# B0_14CN3801.net
KiCad netlist of a schematic drawn in EAGLE
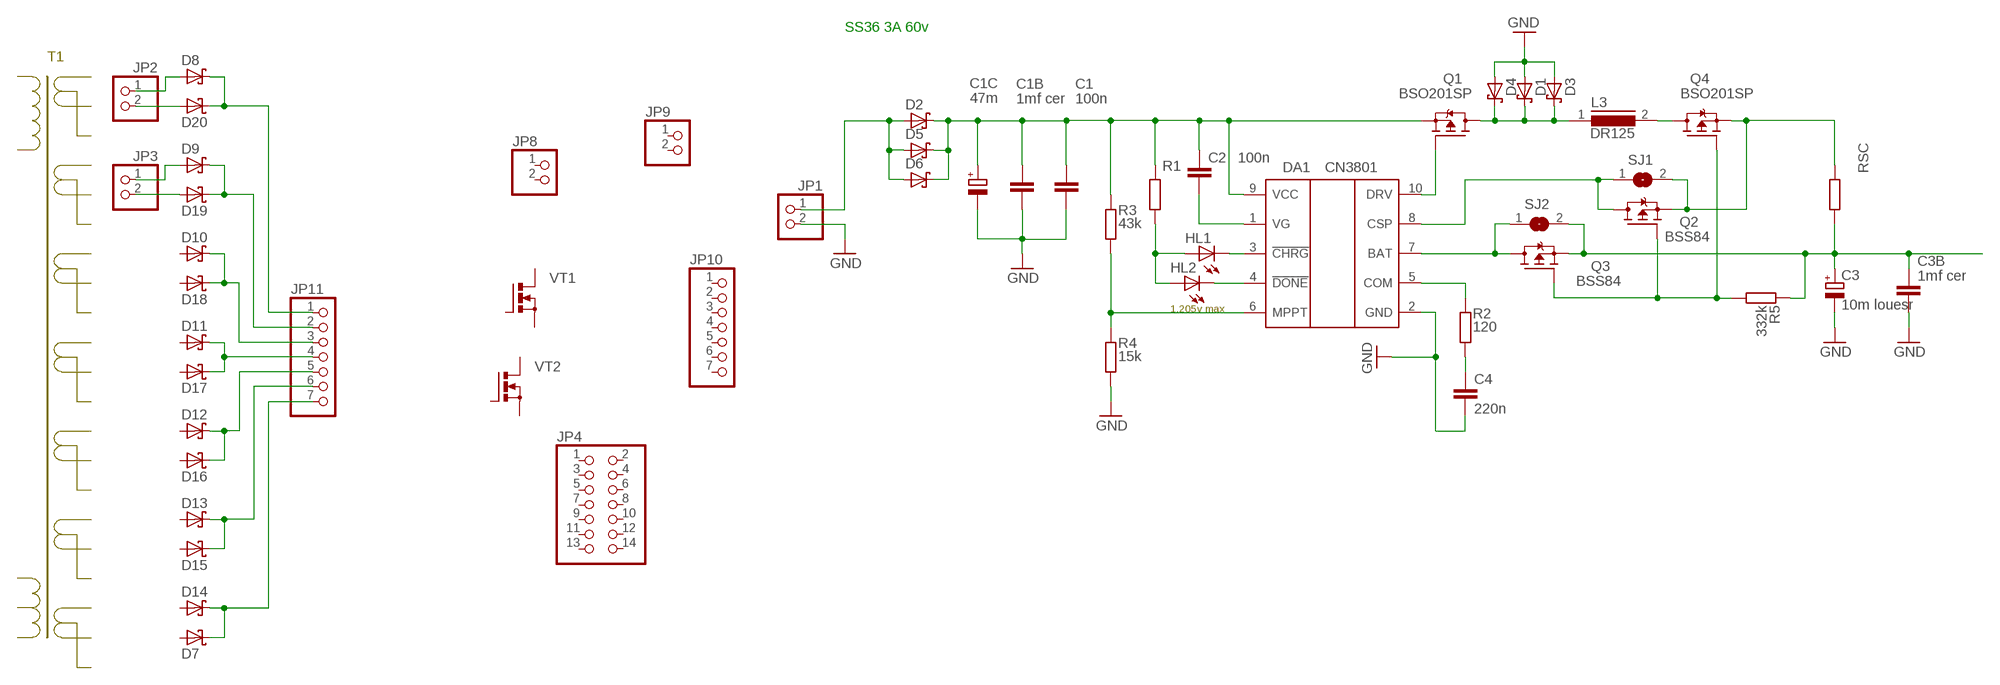
[diagram p0: schematic, sheet 1]

(export (version "E")
  (design (tool "Eeschema 10.0.6"))
  (components
    (comp (ref "C1")
      (value "100n")
      (footprint "eagle-import:C0805")
      (libsource (lib "eagle-import") (part "C-EUC0805"))
    )
    (comp (ref "C1B")
      (value "1mf cer")
      (footprint "eagle-import:C0805")
      (libsource (lib "eagle-import") (part "C-EUC0805"))
    )
    (comp (ref "C1C")
      (value "47m")
      (footprint "eagle-import:E2,5-6")
      (libsource (lib "eagle-import") (part "CPOL-EUE2.5-6"))
    )
    (comp (ref "C2")
      (value "100n")
      (footprint "eagle-import:C0805")
      (libsource (lib "eagle-import") (part "C-EUC0805"))
    )
    (comp (ref "C3")
      (value "10m louesr")
      (footprint "eagle-import:E2,5-6")
      (libsource (lib "eagle-import") (part "CPOL-EUE2.5-6"))
    )
    (comp (ref "C3B")
      (value "1mf cer")
      (footprint "eagle-import:C0805")
      (libsource (lib "eagle-import") (part "C-EUC0805"))
    )
    (comp (ref "C4")
      (value "220n")
      (footprint "eagle-import:C0805")
      (libsource (lib "eagle-import") (part "C-EUC0805"))
    )
    (comp (ref "D1")
      (value "SCHOTTKY-DIODESMC")
      (footprint "eagle-import:SMC")
      (libsource (lib "eagle-import") (part "SCHOTTKY-DIODESMC"))
    )
    (comp (ref "D2")
      (value "SCHOTTKY-DIODESMC")
      (footprint "eagle-import:SMC")
      (libsource (lib "eagle-import") (part "SCHOTTKY-DIODESMC"))
    )
    (comp (ref "D3")
      (value "SCHOTTKY-DIODESMC")
      (footprint "eagle-import:SMC")
      (libsource (lib "eagle-import") (part "SCHOTTKY-DIODESMC"))
    )
    (comp (ref "D4")
      (value "SCHOTTKY-DIODESMC")
      (footprint "eagle-import:SMC")
      (libsource (lib "eagle-import") (part "SCHOTTKY-DIODESMC"))
    )
    (comp (ref "D5")
      (value "SCHOTTKY-DIODESMC")
      (footprint "eagle-import:SMC")
      (libsource (lib "eagle-import") (part "SCHOTTKY-DIODESMC"))
    )
    (comp (ref "D6")
      (value "SCHOTTKY-DIODESMC")
      (footprint "eagle-import:SMC")
      (libsource (lib "eagle-import") (part "SCHOTTKY-DIODESMC"))
    )
    (comp (ref "D7")
      (value "SCHOTTKY-DIODESMC")
      (footprint "eagle-import:SMC")
      (libsource (lib "eagle-import") (part "SCHOTTKY-DIODESMC"))
    )
    (comp (ref "D8")
      (value "SCHOTTKY-DIODESMC")
      (footprint "eagle-import:SMC")
      (libsource (lib "eagle-import") (part "SCHOTTKY-DIODESMC"))
    )
    (comp (ref "D9")
      (value "SCHOTTKY-DIODESMC")
      (footprint "eagle-import:SMC")
      (libsource (lib "eagle-import") (part "SCHOTTKY-DIODESMC"))
    )
    (comp (ref "D10")
      (value "SCHOTTKY-DIODESMC")
      (footprint "eagle-import:SMC")
      (libsource (lib "eagle-import") (part "SCHOTTKY-DIODESMC"))
    )
    (comp (ref "D11")
      (value "SCHOTTKY-DIODESMC")
      (footprint "eagle-import:SMC")
      (libsource (lib "eagle-import") (part "SCHOTTKY-DIODESMC"))
    )
    (comp (ref "D12")
      (value "SCHOTTKY-DIODESMC")
      (footprint "eagle-import:SMC")
      (libsource (lib "eagle-import") (part "SCHOTTKY-DIODESMC"))
    )
    (comp (ref "D13")
      (value "SCHOTTKY-DIODESMC")
      (footprint "eagle-import:SMC")
      (libsource (lib "eagle-import") (part "SCHOTTKY-DIODESMC"))
    )
    (comp (ref "D14")
      (value "SCHOTTKY-DIODESMC")
      (footprint "eagle-import:SMC")
      (libsource (lib "eagle-import") (part "SCHOTTKY-DIODESMC"))
    )
    (comp (ref "D15")
      (value "SCHOTTKY-DIODESMC")
      (footprint "eagle-import:SMC")
      (libsource (lib "eagle-import") (part "SCHOTTKY-DIODESMC"))
    )
    (comp (ref "D16")
      (value "SCHOTTKY-DIODESMC")
      (footprint "eagle-import:SMC")
      (libsource (lib "eagle-import") (part "SCHOTTKY-DIODESMC"))
    )
    (comp (ref "D17")
      (value "SCHOTTKY-DIODESMC")
      (footprint "eagle-import:SMC")
      (libsource (lib "eagle-import") (part "SCHOTTKY-DIODESMC"))
    )
    (comp (ref "D18")
      (value "SCHOTTKY-DIODESMC")
      (footprint "eagle-import:SMC")
      (libsource (lib "eagle-import") (part "SCHOTTKY-DIODESMC"))
    )
    (comp (ref "D19")
      (value "SCHOTTKY-DIODESMC")
      (footprint "eagle-import:SMC")
      (libsource (lib "eagle-import") (part "SCHOTTKY-DIODESMC"))
    )
    (comp (ref "D20")
      (value "SCHOTTKY-DIODESMC")
      (footprint "eagle-import:SMC")
      (libsource (lib "eagle-import") (part "SCHOTTKY-DIODESMC"))
    )
    (comp (ref "DA1")
      (value "CN3801")
      (footprint "eagle-import:SSOP10")
      (libsource (lib "eagle-import") (part "CN3801"))
    )
    (comp (ref "HL1")
      (value "LEDCHIPLED_0603")
      (footprint "eagle-import:CHIPLED_0603")
      (libsource (lib "eagle-import") (part "LEDCHIPLED_0603"))
    )
    (comp (ref "HL2")
      (value "LEDCHIPLED_0603")
      (footprint "eagle-import:CHIPLED_0603")
      (libsource (lib "eagle-import") (part "LEDCHIPLED_0603"))
    )
    (comp (ref "JP1")
      (value "PINHD-1X2/2")
      (footprint "eagle-import:1X02")
      (libsource (lib "eagle-import") (part "PINHD-1X2/2"))
    )
    (comp (ref "JP2")
      (value "PINHD-1X2/2")
      (footprint "eagle-import:1X02")
      (libsource (lib "eagle-import") (part "PINHD-1X2/2"))
    )
    (comp (ref "JP3")
      (value "PINHD-1X2/2")
      (footprint "eagle-import:1X02")
      (libsource (lib "eagle-import") (part "PINHD-1X2/2"))
    )
    (comp (ref "JP4")
      (value "PINHD-2X7")
      (footprint "eagle-import:2X07")
      (libsource (lib "eagle-import") (part "PINHD-2X7"))
    )
    (comp (ref "JP8")
      (value "PINHD-1X2/2")
      (footprint "eagle-import:1X02")
      (libsource (lib "eagle-import") (part "PINHD-1X2/2"))
    )
    (comp (ref "JP9")
      (value "PINHD-1X2/2")
      (footprint "eagle-import:1X02")
      (libsource (lib "eagle-import") (part "PINHD-1X2/2"))
    )
    (comp (ref "JP10")
      (value "PINHD-1X7")
      (footprint "eagle-import:1X07")
      (libsource (lib "eagle-import") (part "PINHD-1X7"))
    )
    (comp (ref "JP11")
      (value "PINHD-1X7")
      (footprint "eagle-import:1X07")
      (libsource (lib "eagle-import") (part "PINHD-1X7"))
    )
    (comp (ref "L3")
      (value "DR125")
      (footprint "eagle-import:DR125")
      (libsource (lib "eagle-import") (part "DR125"))
    )
    (comp (ref "Q1")
      (value "BSO201SP")
      (footprint "eagle-import:SO-8")
      (libsource (lib "eagle-import") (part "BSO201SP"))
    )
    (comp (ref "Q2")
      (value "BSS84")
      (footprint "eagle-import:SC75_INFINEON")
      (libsource (lib "eagle-import") (part "BSA223SP"))
    )
    (comp (ref "Q3")
      (value "BSS84")
      (footprint "eagle-import:SC75_INFINEON")
      (libsource (lib "eagle-import") (part "BSA223SP"))
    )
    (comp (ref "Q4")
      (value "BSO201SP")
      (footprint "eagle-import:SO-8")
      (libsource (lib "eagle-import") (part "BSO201SP"))
    )
    (comp (ref "R1")
      (value "R-EU_R0805")
      (footprint "eagle-import:R0805")
      (libsource (lib "eagle-import") (part "R-EU_R0805"))
    )
    (comp (ref "R2")
      (value "120")
      (footprint "eagle-import:R0805")
      (libsource (lib "eagle-import") (part "R-EU_R0805"))
    )
    (comp (ref "R3")
      (value "43k")
      (footprint "eagle-import:R0805")
      (libsource (lib "eagle-import") (part "R-EU_R0805"))
    )
    (comp (ref "R4")
      (value "15k")
      (footprint "eagle-import:R0805")
      (libsource (lib "eagle-import") (part "R-EU_R0805"))
    )
    (comp (ref "R5")
      (value "332k")
      (footprint "eagle-import:R0805")
      (libsource (lib "eagle-import") (part "R-EU_R0805"))
    )
    (comp (ref "RSC")
      (value "R-EU_R0805")
      (footprint "eagle-import:R0805")
      (libsource (lib "eagle-import") (part "R-EU_R0805"))
    )
    (comp (ref "SJ1") (value "SJ") (footprint "eagle-import:SJ") (libsource (lib "eagle-import") (part "SJ")))
    (comp (ref "SJ2") (value "SJ") (footprint "eagle-import:SJ") (libsource (lib "eagle-import") (part "SJ")))
    (comp (ref "VT1")
      (value "MOSFET-N_TO220_H")
      (footprint "eagle-import:TO220BH")
      (libsource (lib "eagle-import") (part "MOSFET-N_TO220_H"))
    )
    (comp (ref "VT2")
      (value "MOSFET-N_TO220_H")
      (footprint "eagle-import:TO220BH")
      (libsource (lib "eagle-import") (part "MOSFET-N_TO220_H"))
    )
  )
  (nets
    (net (code "1") (name "GND") (class "Default")
      (node (ref "C1") (pin "2") (pinfunction "2_2") (pintype "passive"))
      (node (ref "C1B") (pin "2") (pinfunction "2_2") (pintype "passive"))
      (node (ref "C1C") (pin "-") (pinfunction "-_-") (pintype "passive"))
      (node (ref "C3") (pin "-") (pinfunction "-_-") (pintype "passive"))
      (node (ref "C3B") (pin "2") (pinfunction "2_2") (pintype "passive"))
      (node (ref "C4") (pin "2") (pinfunction "2_2") (pintype "passive"))
      (node (ref "D1") (pin "A") (pinfunction "A_A") (pintype "passive"))
      (node (ref "D3") (pin "A") (pinfunction "A_A") (pintype "passive"))
      (node (ref "D4") (pin "A") (pinfunction "A_A") (pintype "passive"))
      (node (ref "DA1") (pin "2") (pinfunction "GND_2") (pintype "power_in"))
      (node (ref "JP1") (pin "2") (pinfunction "2_2") (pintype "passive"))
      (node (ref "R4") (pin "1") (pinfunction "1_1") (pintype "passive"))
    )
    (net (code "2") (name "Net-(C4-Pad1)") (class "Default")
      (node (ref "C4") (pin "1") (pinfunction "1_1") (pintype "passive"))
      (node (ref "R2") (pin "1") (pinfunction "1_1") (pintype "passive"))
    )
    (net (code "3") (name "Net-(D1-PadC)") (class "Default")
      (node (ref "D1") (pin "C") (pinfunction "C_C") (pintype "passive"))
      (node (ref "D3") (pin "C") (pinfunction "C_C") (pintype "passive"))
      (node (ref "D4") (pin "C") (pinfunction "C_C") (pintype "passive"))
      (node (ref "L3") (pin "1") (pinfunction "1_1") (pintype "passive"))
      (node (ref "Q1") (pin "5") (pinfunction "D_5") (pintype "passive"))
      (node (ref "Q1") (pin "6") (pinfunction "D_6") (pintype "passive"))
      (node (ref "Q1") (pin "7") (pinfunction "D_7") (pintype "passive"))
      (node (ref "Q1") (pin "8") (pinfunction "D_8") (pintype "passive"))
    )
    (net (code "4") (name "Net-(D2-PadA)") (class "Default")
      (node (ref "D2") (pin "A") (pinfunction "A_A") (pintype "passive"))
      (node (ref "D5") (pin "A") (pinfunction "A_A") (pintype "passive"))
      (node (ref "D6") (pin "A") (pinfunction "A_A") (pintype "passive"))
      (node (ref "JP1") (pin "1") (pinfunction "1_1") (pintype "passive"))
    )
    (net (code "5") (name "Net-(D8-PadA)") (class "Default")
      (node (ref "D8") (pin "A") (pinfunction "A_A") (pintype "passive"))
      (node (ref "JP2") (pin "1") (pinfunction "1_1") (pintype "passive"))
    )
    (net (code "6") (name "Net-(D9-PadA)") (class "Default")
      (node (ref "D9") (pin "A") (pinfunction "A_A") (pintype "passive"))
      (node (ref "JP3") (pin "1") (pinfunction "1_1") (pintype "passive"))
    )
    (net (code "7") (name "Net-(D10-PadC)") (class "Default")
      (node (ref "D10") (pin "C") (pinfunction "C_C") (pintype "passive"))
      (node (ref "D18") (pin "C") (pinfunction "C_C") (pintype "passive"))
      (node (ref "JP11") (pin "3") (pinfunction "3_3") (pintype "passive"))
    )
    (net (code "8") (name "Net-(D11-PadC)") (class "Default")
      (node (ref "D11") (pin "C") (pinfunction "C_C") (pintype "passive"))
      (node (ref "D17") (pin "C") (pinfunction "C_C") (pintype "passive"))
      (node (ref "JP11") (pin "4") (pinfunction "4_4") (pintype "passive"))
    )
    (net (code "9") (name "Net-(D12-PadC)") (class "Default")
      (node (ref "D12") (pin "C") (pinfunction "C_C") (pintype "passive"))
      (node (ref "D16") (pin "C") (pinfunction "C_C") (pintype "passive"))
      (node (ref "JP11") (pin "5") (pinfunction "5_5") (pintype "passive"))
    )
    (net (code "10") (name "Net-(D13-PadC)") (class "Default")
      (node (ref "D13") (pin "C") (pinfunction "C_C") (pintype "passive"))
      (node (ref "D15") (pin "C") (pinfunction "C_C") (pintype "passive"))
      (node (ref "JP11") (pin "6") (pinfunction "6_6") (pintype "passive"))
    )
    (net (code "11") (name "Net-(D14-PadC)") (class "Default")
      (node (ref "D14") (pin "C") (pinfunction "C_C") (pintype "passive"))
      (node (ref "D7") (pin "C") (pinfunction "C_C") (pintype "passive"))
      (node (ref "JP11") (pin "7") (pinfunction "7_7") (pintype "passive"))
    )
    (net (code "12") (name "Net-(D19-PadA)") (class "Default")
      (node (ref "D19") (pin "A") (pinfunction "A_A") (pintype "passive"))
      (node (ref "JP3") (pin "2") (pinfunction "2_2") (pintype "passive"))
    )
    (net (code "13") (name "Net-(D19-PadC)") (class "Default")
      (node (ref "D19") (pin "C") (pinfunction "C_C") (pintype "passive"))
      (node (ref "D9") (pin "C") (pinfunction "C_C") (pintype "passive"))
      (node (ref "JP11") (pin "2") (pinfunction "2_2") (pintype "passive"))
    )
    (net (code "14") (name "Net-(D20-PadA)") (class "Default")
      (node (ref "D20") (pin "A") (pinfunction "A_A") (pintype "passive"))
      (node (ref "JP2") (pin "2") (pinfunction "2_2") (pintype "passive"))
    )
    (net (code "15") (name "Net-(D20-PadC)") (class "Default")
      (node (ref "D20") (pin "C") (pinfunction "C_C") (pintype "passive"))
      (node (ref "D8") (pin "C") (pinfunction "C_C") (pintype "passive"))
      (node (ref "JP11") (pin "1") (pinfunction "1_1") (pintype "passive"))
    )
    (net (code "16") (name "Net-(DA1-BAT)") (class "Default")
      (node (ref "DA1") (pin "7") (pinfunction "BAT_7") (pintype "output"))
      (node (ref "Q3") (pin "2") (pinfunction "D_2") (pintype "passive"))
      (node (ref "SJ2") (pin "1") (pinfunction "1_1") (pintype "passive"))
    )
    (net (code "17") (name "Net-(DA1-COM)") (class "Default")
      (node (ref "DA1") (pin "5") (pinfunction "COM_5") (pintype "output"))
      (node (ref "R2") (pin "2") (pinfunction "2_2") (pintype "passive"))
    )
    (net (code "18") (name "Net-(DA1-CSP)") (class "Default")
      (node (ref "DA1") (pin "8") (pinfunction "CSP_8") (pintype "output"))
      (node (ref "Q2") (pin "2") (pinfunction "D_2") (pintype "passive"))
      (node (ref "SJ1") (pin "1") (pinfunction "1_1") (pintype "passive"))
    )
    (net (code "19") (name "Net-(DA1-DRV)") (class "Default")
      (node (ref "DA1") (pin "10") (pinfunction "DRV_10") (pintype "output"))
      (node (ref "Q1") (pin "4") (pinfunction "G_4") (pintype "passive"))
    )
    (net (code "20") (name "Net-(DA1-MPPT)") (class "Default")
      (node (ref "DA1") (pin "6") (pinfunction "MPPT_6") (pintype "input"))
      (node (ref "R3") (pin "1") (pinfunction "1_1") (pintype "passive"))
      (node (ref "R4") (pin "2") (pinfunction "2_2") (pintype "passive"))
    )
    (net (code "21") (name "Net-(DA1-VCC)") (class "Default")
      (node (ref "C1") (pin "1") (pinfunction "1_1") (pintype "passive"))
      (node (ref "C1B") (pin "1") (pinfunction "1_1") (pintype "passive"))
      (node (ref "C1C") (pin "+") (pinfunction "+_+") (pintype "passive"))
      (node (ref "C2") (pin "1") (pinfunction "1_1") (pintype "passive"))
      (node (ref "D2") (pin "C") (pinfunction "C_C") (pintype "passive"))
      (node (ref "D5") (pin "C") (pinfunction "C_C") (pintype "passive"))
      (node (ref "D6") (pin "C") (pinfunction "C_C") (pintype "passive"))
      (node (ref "DA1") (pin "9") (pinfunction "VCC_9") (pintype "power_in"))
      (node (ref "Q1") (pin "1") (pinfunction "S_1") (pintype "passive"))
      (node (ref "Q1") (pin "2") (pinfunction "S_2") (pintype "passive"))
      (node (ref "Q1") (pin "3") (pinfunction "S_3") (pintype "passive"))
      (node (ref "R1") (pin "2") (pinfunction "2_2") (pintype "passive"))
      (node (ref "R3") (pin "2") (pinfunction "2_2") (pintype "passive"))
    )
    (net (code "22") (name "Net-(DA1-VG)") (class "Default")
      (node (ref "C2") (pin "2") (pinfunction "2_2") (pintype "passive"))
      (node (ref "DA1") (pin "1") (pinfunction "VG_1") (pintype "input"))
    )
    (net (code "23") (name "Net-(DA1-~{CHRG})") (class "Default")
      (node (ref "DA1") (pin "3") (pinfunction "~{CHRG}_3") (pintype "output"))
      (node (ref "HL1") (pin "C") (pinfunction "C_C") (pintype "passive"))
    )
    (net (code "24") (name "Net-(DA1-~{DONE})") (class "Default")
      (node (ref "DA1") (pin "4") (pinfunction "~{DONE}_4") (pintype "output"))
      (node (ref "HL2") (pin "C") (pinfunction "C_C") (pintype "passive"))
    )
    (net (code "25") (name "Net-(HL1-PadA)") (class "Default")
      (node (ref "HL1") (pin "A") (pinfunction "A_A") (pintype "passive"))
      (node (ref "HL2") (pin "A") (pinfunction "A_A") (pintype "passive"))
      (node (ref "R1") (pin "1") (pinfunction "1_1") (pintype "passive"))
    )
    (net (code "26") (name "Net-(L3-Pad2)") (class "Default")
      (node (ref "L3") (pin "2") (pinfunction "2_2") (pintype "passive"))
      (node (ref "Q4") (pin "5") (pinfunction "D_5") (pintype "passive"))
      (node (ref "Q4") (pin "6") (pinfunction "D_6") (pintype "passive"))
      (node (ref "Q4") (pin "7") (pinfunction "D_7") (pintype "passive"))
      (node (ref "Q4") (pin "8") (pinfunction "D_8") (pintype "passive"))
    )
    (net (code "27") (name "Net-(Q2-G)") (class "Default")
      (node (ref "Q2") (pin "1") (pinfunction "G_1") (pintype "passive"))
      (node (ref "Q3") (pin "1") (pinfunction "G_1") (pintype "passive"))
      (node (ref "Q4") (pin "4") (pinfunction "G_4") (pintype "passive"))
      (node (ref "R5") (pin "1") (pinfunction "1_1") (pintype "passive"))
    )
    (net (code "28") (name "Net-(Q2-S)") (class "Default")
      (node (ref "Q2") (pin "3") (pinfunction "S_3") (pintype "passive"))
      (node (ref "Q4") (pin "1") (pinfunction "S_1") (pintype "passive"))
      (node (ref "Q4") (pin "2") (pinfunction "S_2") (pintype "passive"))
      (node (ref "Q4") (pin "3") (pinfunction "S_3") (pintype "passive"))
      (node (ref "RSC") (pin "2") (pinfunction "2_2") (pintype "passive"))
      (node (ref "SJ1") (pin "2") (pinfunction "2_2") (pintype "passive"))
    )
    (net (code "29") (name "Net-(Q3-S)") (class "Default")
      (node (ref "C3") (pin "+") (pinfunction "+_+") (pintype "passive"))
      (node (ref "C3B") (pin "1") (pinfunction "1_1") (pintype "passive"))
      (node (ref "Q3") (pin "3") (pinfunction "S_3") (pintype "passive"))
      (node (ref "R5") (pin "2") (pinfunction "2_2") (pintype "passive"))
      (node (ref "RSC") (pin "1") (pinfunction "1_1") (pintype "passive"))
      (node (ref "SJ2") (pin "2") (pinfunction "2_2") (pintype "passive"))
    )
    (net (code "30") (name "unconnected-(D7-PadA)") (class "Default")
      (node (ref "D7") (pin "A") (pinfunction "A_A") (pintype "passive"))
    )
    (net (code "31") (name "unconnected-(D10-PadA)") (class "Default")
      (node (ref "D10") (pin "A") (pinfunction "A_A") (pintype "passive"))
    )
    (net (code "32") (name "unconnected-(D11-PadA)") (class "Default")
      (node (ref "D11") (pin "A") (pinfunction "A_A") (pintype "passive"))
    )
    (net (code "33") (name "unconnected-(D12-PadA)") (class "Default")
      (node (ref "D12") (pin "A") (pinfunction "A_A") (pintype "passive"))
    )
    (net (code "34") (name "unconnected-(D13-PadA)") (class "Default")
      (node (ref "D13") (pin "A") (pinfunction "A_A") (pintype "passive"))
    )
    (net (code "35") (name "unconnected-(D14-PadA)") (class "Default")
      (node (ref "D14") (pin "A") (pinfunction "A_A") (pintype "passive"))
    )
    (net (code "36") (name "unconnected-(D15-PadA)") (class "Default")
      (node (ref "D15") (pin "A") (pinfunction "A_A") (pintype "passive"))
    )
    (net (code "37") (name "unconnected-(D16-PadA)") (class "Default")
      (node (ref "D16") (pin "A") (pinfunction "A_A") (pintype "passive"))
    )
    (net (code "38") (name "unconnected-(D17-PadA)") (class "Default")
      (node (ref "D17") (pin "A") (pinfunction "A_A") (pintype "passive"))
    )
    (net (code "39") (name "unconnected-(D18-PadA)") (class "Default")
      (node (ref "D18") (pin "A") (pinfunction "A_A") (pintype "passive"))
    )
    (net (code "40") (name "unconnected-(JP4-Pad1)") (class "Default")
      (node (ref "JP4") (pin "1") (pinfunction "1_1") (pintype "passive"))
    )
    (net (code "41") (name "unconnected-(JP4-Pad2)") (class "Default")
      (node (ref "JP4") (pin "2") (pinfunction "2_2") (pintype "passive"))
    )
    (net (code "42") (name "unconnected-(JP4-Pad3)") (class "Default")
      (node (ref "JP4") (pin "3") (pinfunction "3_3") (pintype "passive"))
    )
    (net (code "43") (name "unconnected-(JP4-Pad4)") (class "Default")
      (node (ref "JP4") (pin "4") (pinfunction "4_4") (pintype "passive"))
    )
    (net (code "44") (name "unconnected-(JP4-Pad5)") (class "Default")
      (node (ref "JP4") (pin "5") (pinfunction "5_5") (pintype "passive"))
    )
    (net (code "45") (name "unconnected-(JP4-Pad6)") (class "Default")
      (node (ref "JP4") (pin "6") (pinfunction "6_6") (pintype "passive"))
    )
    (net (code "46") (name "unconnected-(JP4-Pad7)") (class "Default")
      (node (ref "JP4") (pin "7") (pinfunction "7_7") (pintype "passive"))
    )
    (net (code "47") (name "unconnected-(JP4-Pad8)") (class "Default")
      (node (ref "JP4") (pin "8") (pinfunction "8_8") (pintype "passive"))
    )
    (net (code "48") (name "unconnected-(JP4-Pad9)") (class "Default")
      (node (ref "JP4") (pin "9") (pinfunction "9_9") (pintype "passive"))
    )
    (net (code "49") (name "unconnected-(JP4-Pad10)") (class "Default")
      (node (ref "JP4") (pin "10") (pinfunction "10_10") (pintype "passive"))
    )
    (net (code "50") (name "unconnected-(JP4-Pad11)") (class "Default")
      (node (ref "JP4") (pin "11") (pinfunction "11_11") (pintype "passive"))
    )
    (net (code "51") (name "unconnected-(JP4-Pad12)") (class "Default")
      (node (ref "JP4") (pin "12") (pinfunction "12_12") (pintype "passive"))
    )
    (net (code "52") (name "unconnected-(JP4-Pad13)") (class "Default")
      (node (ref "JP4") (pin "13") (pinfunction "13_13") (pintype "passive"))
    )
    (net (code "53") (name "unconnected-(JP4-Pad14)") (class "Default")
      (node (ref "JP4") (pin "14") (pinfunction "14_14") (pintype "passive"))
    )
    (net (code "54") (name "unconnected-(JP8-Pad1)") (class "Default")
      (node (ref "JP8") (pin "1") (pinfunction "1_1") (pintype "passive"))
    )
    (net (code "55") (name "unconnected-(JP8-Pad2)") (class "Default")
      (node (ref "JP8") (pin "2") (pinfunction "2_2") (pintype "passive"))
    )
    (net (code "56") (name "unconnected-(JP9-Pad1)") (class "Default")
      (node (ref "JP9") (pin "1") (pinfunction "1_1") (pintype "passive"))
    )
    (net (code "57") (name "unconnected-(JP9-Pad2)") (class "Default")
      (node (ref "JP9") (pin "2") (pinfunction "2_2") (pintype "passive"))
    )
    (net (code "58") (name "unconnected-(JP10-Pad1)") (class "Default")
      (node (ref "JP10") (pin "1") (pinfunction "1_1") (pintype "passive"))
    )
    (net (code "59") (name "unconnected-(JP10-Pad2)") (class "Default")
      (node (ref "JP10") (pin "2") (pinfunction "2_2") (pintype "passive"))
    )
    (net (code "60") (name "unconnected-(JP10-Pad3)") (class "Default")
      (node (ref "JP10") (pin "3") (pinfunction "3_3") (pintype "passive"))
    )
    (net (code "61") (name "unconnected-(JP10-Pad4)") (class "Default")
      (node (ref "JP10") (pin "4") (pinfunction "4_4") (pintype "passive"))
    )
    (net (code "62") (name "unconnected-(JP10-Pad5)") (class "Default")
      (node (ref "JP10") (pin "5") (pinfunction "5_5") (pintype "passive"))
    )
    (net (code "63") (name "unconnected-(JP10-Pad6)") (class "Default")
      (node (ref "JP10") (pin "6") (pinfunction "6_6") (pintype "passive"))
    )
    (net (code "64") (name "unconnected-(JP10-Pad7)") (class "Default")
      (node (ref "JP10") (pin "7") (pinfunction "7_7") (pintype "passive"))
    )
    (net (code "65") (name "unconnected-(VT1-PadD)") (class "Default")
      (node (ref "VT1") (pin "D") (pinfunction "D_D") (pintype "passive"))
    )
    (net (code "66") (name "unconnected-(VT1-PadG)") (class "Default")
      (node (ref "VT1") (pin "G") (pinfunction "G_G") (pintype "passive"))
    )
    (net (code "67") (name "unconnected-(VT1-PadS)") (class "Default")
      (node (ref "VT1") (pin "S") (pinfunction "S_S") (pintype "passive"))
    )
    (net (code "68") (name "unconnected-(VT2-PadD)") (class "Default")
      (node (ref "VT2") (pin "D") (pinfunction "D_D") (pintype "passive"))
    )
    (net (code "69") (name "unconnected-(VT2-PadG)") (class "Default")
      (node (ref "VT2") (pin "G") (pinfunction "G_G") (pintype "passive"))
    )
    (net (code "70") (name "unconnected-(VT2-PadS)") (class "Default")
      (node (ref "VT2") (pin "S") (pinfunction "S_S") (pintype "passive"))
    )
  )
)
